# PCB_7_3D.net
KiCad netlist of a schematic drawn in EasyEDA
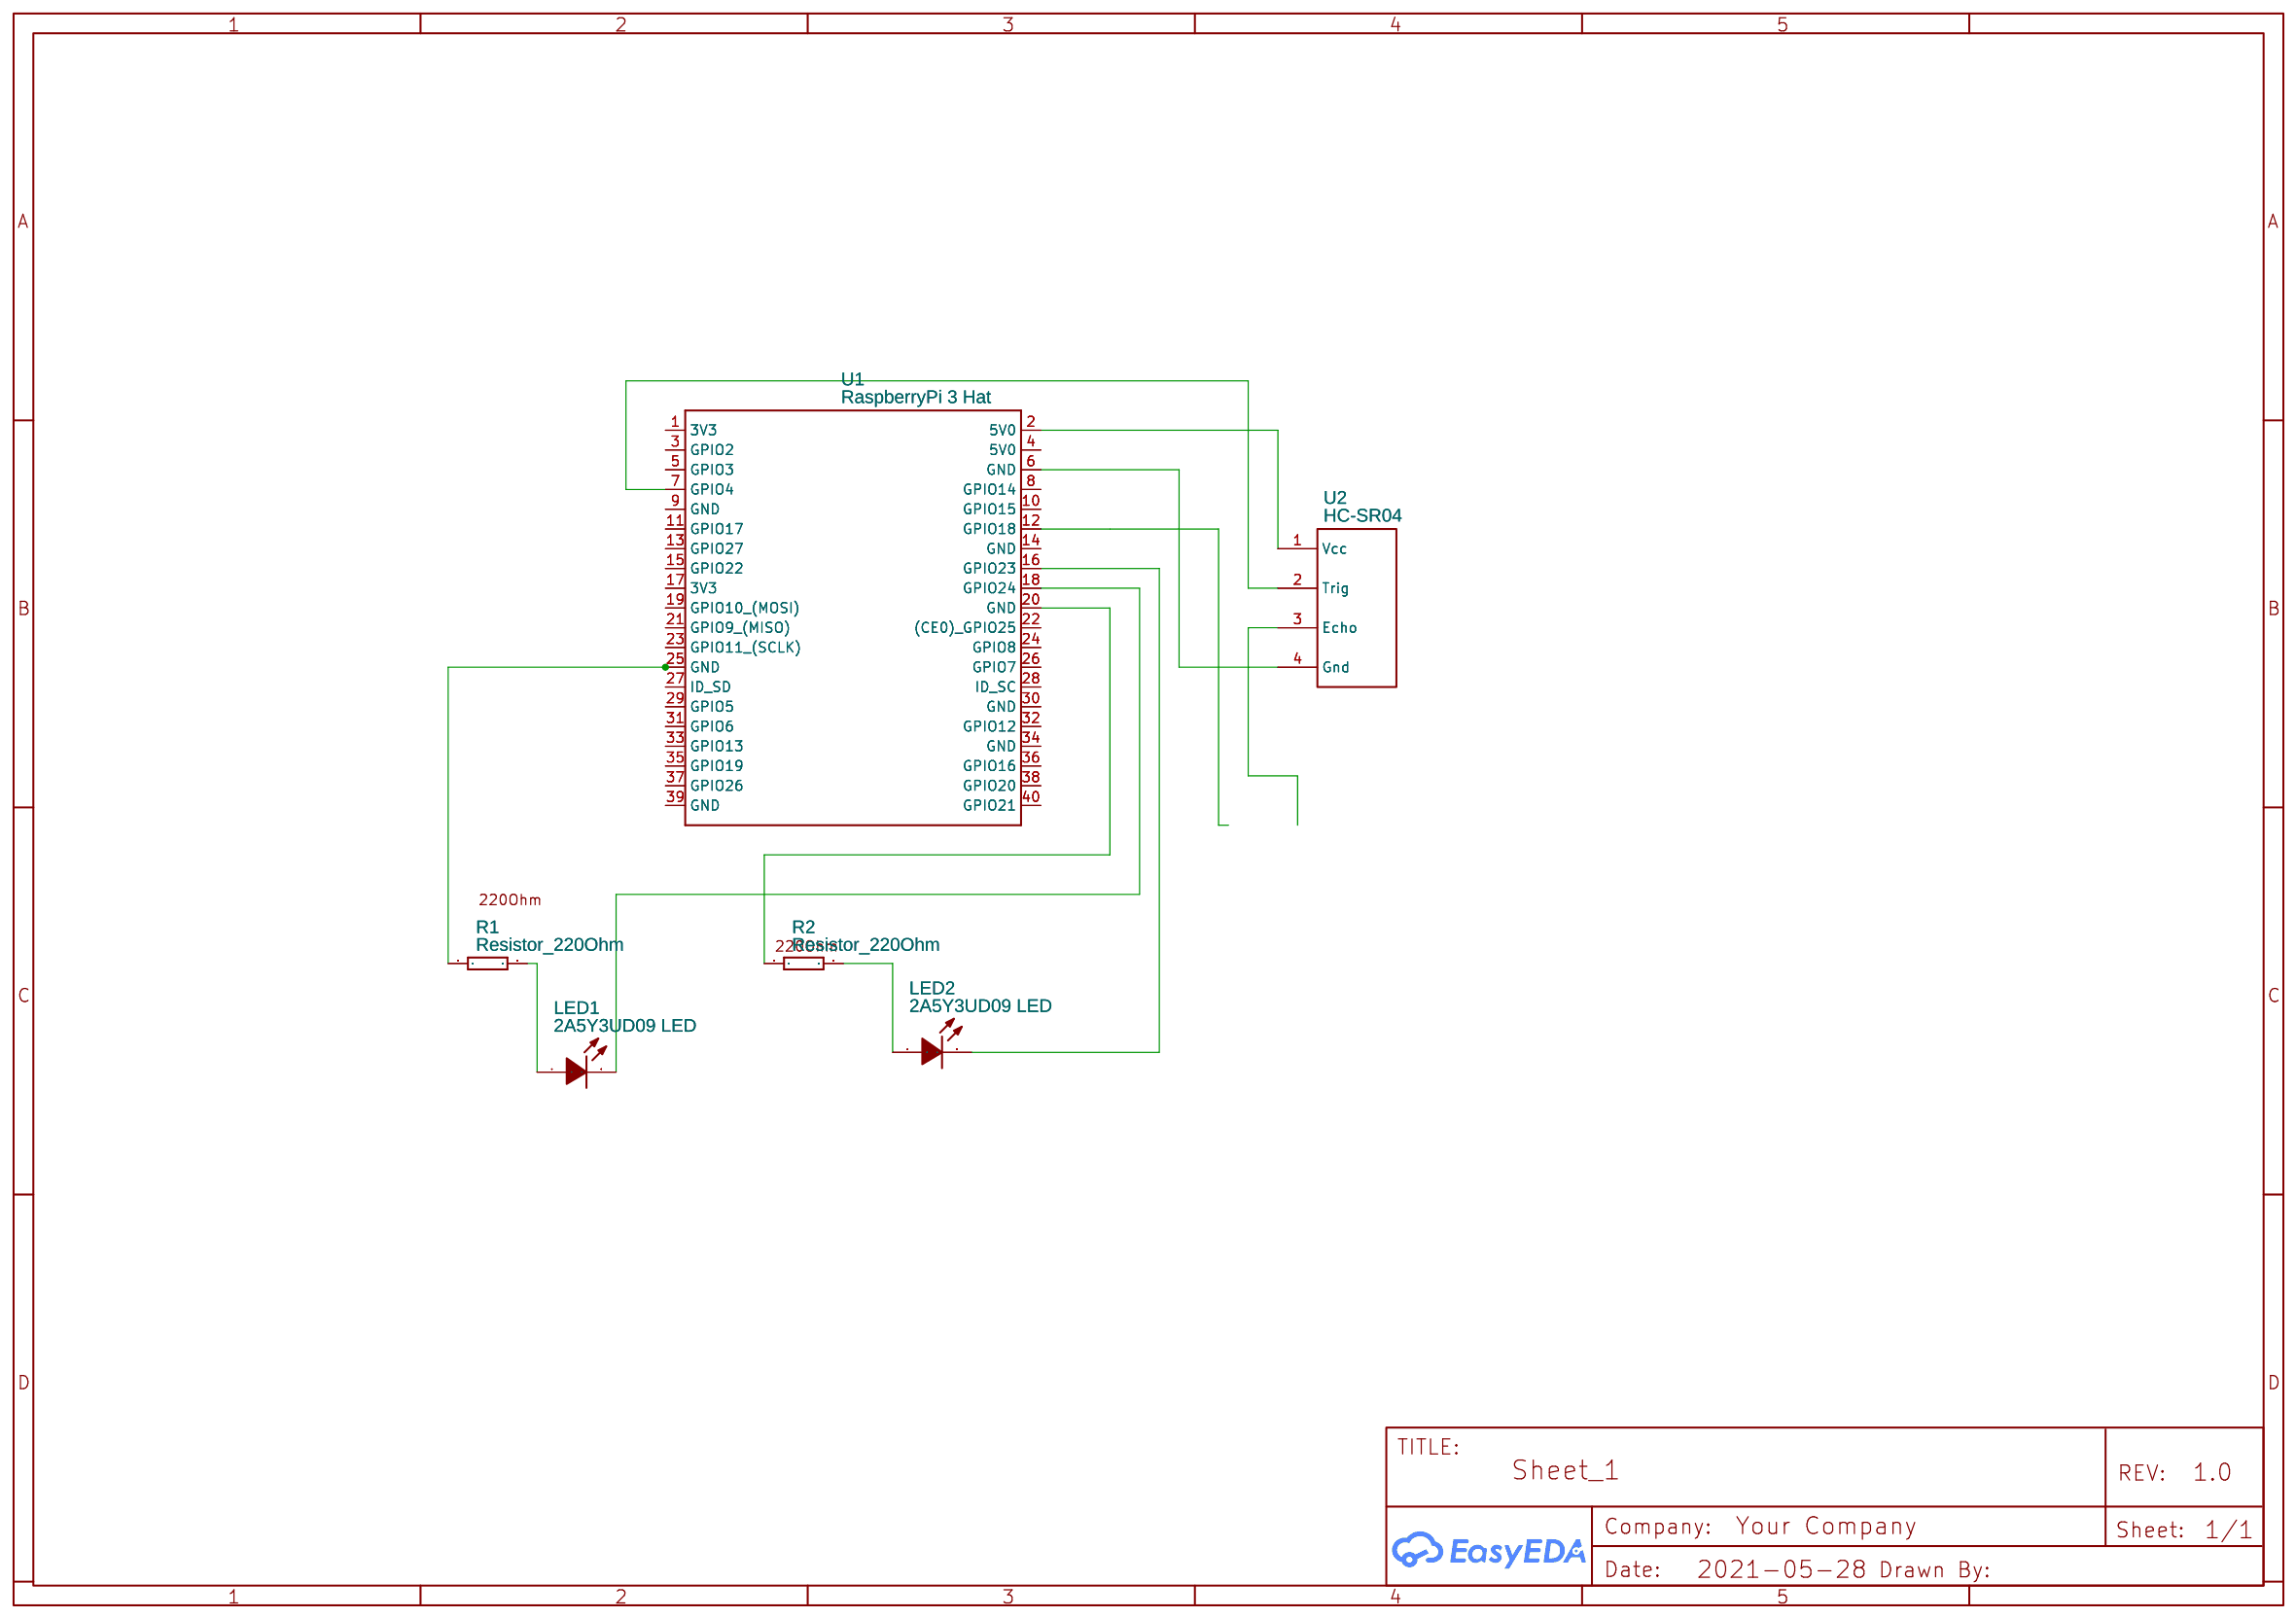
[diagram p0: schematic sheet]

(export (version "E")
  (design (tool "Eeschema 10.0.6"))
  (components
    (comp (ref "LED1")
      (value "2A5Y3UD09 LED")
      (fields (field (name "BOM_Supplier Part") "C3651"))
      (libsource (lib "") (part "2A5Y3UD09 LED"))
    )
    (comp (ref "LED2")
      (value "2A5Y3UD09 LED")
      (fields (field (name "BOM_Supplier Part") "C3651"))
      (libsource (lib "") (part "2A5Y3UD09 LED"))
    )
    (comp (ref "R1") (value "Resistor_220Ohm") (libsource (lib "") (part "Resistor_220Ohm_1")))
    (comp (ref "R2") (value "Resistor_220Ohm") (libsource (lib "") (part "Resistor_220Ohm")))
    (comp (ref "U1")
      (value "RaspberryPi 3 Hat")
      (fields (field (name "BOM_Manufacturer Part") "RaspberryPi 3"))
      (libsource (lib "") (part "RaspberryPi 3 Hat"))
    )
    (comp (ref "U2") (value "HC-SR04") (libsource (lib "") (part "HC-SR04")))
  )
  (nets
    (net (code "1") (name "Net-(LED1-+)") (class "Default")
      (node (ref "LED1") (pin "1") (pinfunction "+_1") (pintype "unspecified"))
      (node (ref "R1") (pin "2") (pinfunction "2_2") (pintype "unspecified"))
    )
    (net (code "2") (name "Net-(LED1--)") (class "Default")
      (node (ref "LED1") (pin "2") (pinfunction "-_2") (pintype "unspecified"))
      (node (ref "U1") (pin "18") (pinfunction "GPIO24_18") (pintype "unspecified"))
    )
    (net (code "3") (name "Net-(LED2-+)") (class "Default")
      (node (ref "LED2") (pin "1") (pinfunction "+_1") (pintype "unspecified"))
      (node (ref "R2") (pin "2") (pinfunction "2_2") (pintype "unspecified"))
    )
    (net (code "4") (name "Net-(LED2--)") (class "Default")
      (node (ref "LED2") (pin "2") (pinfunction "-_2") (pintype "unspecified"))
      (node (ref "U1") (pin "16") (pinfunction "GPIO23_16") (pintype "unspecified"))
    )
    (net (code "5") (name "Net-(R1-Pad1)") (class "Default")
      (node (ref "R1") (pin "1") (pinfunction "1_1") (pintype "unspecified"))
      (node (ref "U1") (pin "25") (pinfunction "GND_25") (pintype "unspecified"))
    )
    (net (code "6") (name "Net-(R2-Pad1)") (class "Default")
      (node (ref "R2") (pin "1") (pinfunction "1_1") (pintype "unspecified"))
      (node (ref "U1") (pin "20") (pinfunction "GND_20") (pintype "unspecified"))
    )
    (net (code "7") (name "Net-(U1-GPIO4)") (class "Default")
      (node (ref "U1") (pin "7") (pinfunction "GPIO4_7") (pintype "unspecified"))
      (node (ref "U2") (pin "2") (pinfunction "Trig_2") (pintype "unspecified"))
    )
    (net (code "8") (name "Net-(U2-Gnd)") (class "Default")
      (node (ref "U1") (pin "6") (pinfunction "GND_6") (pintype "unspecified"))
      (node (ref "U2") (pin "4") (pinfunction "Gnd_4") (pintype "unspecified"))
    )
    (net (code "9") (name "Net-(U2-Vcc)") (class "Default")
      (node (ref "U1") (pin "2") (pinfunction "5V0_2") (pintype "unspecified"))
      (node (ref "U2") (pin "1") (pinfunction "Vcc_1") (pintype "unspecified"))
    )
    (net (code "10") (name "unconnected-(U1-(CE0)_GPIO25-Pad22)") (class "Default")
      (node (ref "U1") (pin "22") (pinfunction "(CE0)_GPIO25_22") (pintype "unspecified"))
    )
    (net (code "11") (name "unconnected-(U1-3V3-Pad1)") (class "Default")
      (node (ref "U1") (pin "1") (pinfunction "3V3_1") (pintype "unspecified"))
    )
    (net (code "12") (name "unconnected-(U1-3V3-Pad17)") (class "Default")
      (node (ref "U1") (pin "17") (pinfunction "3V3_17") (pintype "unspecified"))
    )
    (net (code "13") (name "unconnected-(U1-5V0-Pad4)") (class "Default")
      (node (ref "U1") (pin "4") (pinfunction "5V0_4") (pintype "unspecified"))
    )
    (net (code "14") (name "unconnected-(U1-GND-Pad9)") (class "Default")
      (node (ref "U1") (pin "9") (pinfunction "GND_9") (pintype "unspecified"))
    )
    (net (code "15") (name "unconnected-(U1-GND-Pad14)") (class "Default")
      (node (ref "U1") (pin "14") (pinfunction "GND_14") (pintype "unspecified"))
    )
    (net (code "16") (name "unconnected-(U1-GND-Pad30)") (class "Default")
      (node (ref "U1") (pin "30") (pinfunction "GND_30") (pintype "unspecified"))
    )
    (net (code "17") (name "unconnected-(U1-GND-Pad34)") (class "Default")
      (node (ref "U1") (pin "34") (pinfunction "GND_34") (pintype "unspecified"))
    )
    (net (code "18") (name "unconnected-(U1-GND-Pad39)") (class "Default")
      (node (ref "U1") (pin "39") (pinfunction "GND_39") (pintype "unspecified"))
    )
    (net (code "19") (name "unconnected-(U1-GPIO2-Pad3)") (class "Default")
      (node (ref "U1") (pin "3") (pinfunction "GPIO2_3") (pintype "unspecified"))
    )
    (net (code "20") (name "unconnected-(U1-GPIO3-Pad5)") (class "Default")
      (node (ref "U1") (pin "5") (pinfunction "GPIO3_5") (pintype "unspecified"))
    )
    (net (code "21") (name "unconnected-(U1-GPIO5-Pad29)") (class "Default")
      (node (ref "U1") (pin "29") (pinfunction "GPIO5_29") (pintype "unspecified"))
    )
    (net (code "22") (name "unconnected-(U1-GPIO6-Pad31)") (class "Default")
      (node (ref "U1") (pin "31") (pinfunction "GPIO6_31") (pintype "unspecified"))
    )
    (net (code "23") (name "unconnected-(U1-GPIO7-Pad26)") (class "Default")
      (node (ref "U1") (pin "26") (pinfunction "GPIO7_26") (pintype "unspecified"))
    )
    (net (code "24") (name "unconnected-(U1-GPIO8-Pad24)") (class "Default")
      (node (ref "U1") (pin "24") (pinfunction "GPIO8_24") (pintype "unspecified"))
    )
    (net (code "25") (name "unconnected-(U1-GPIO9_(MISO)-Pad21)") (class "Default")
      (node (ref "U1") (pin "21") (pinfunction "GPIO9_(MISO)_21") (pintype "unspecified"))
    )
    (net (code "26") (name "unconnected-(U1-GPIO10_(MOSI)-Pad19)") (class "Default")
      (node (ref "U1") (pin "19") (pinfunction "GPIO10_(MOSI)_19") (pintype "unspecified"))
    )
    (net (code "27") (name "unconnected-(U1-GPIO11_(SCLK)-Pad23)") (class "Default")
      (node (ref "U1") (pin "23") (pinfunction "GPIO11_(SCLK)_23") (pintype "unspecified"))
    )
    (net (code "28") (name "unconnected-(U1-GPIO12-Pad32)") (class "Default")
      (node (ref "U1") (pin "32") (pinfunction "GPIO12_32") (pintype "unspecified"))
    )
    (net (code "29") (name "unconnected-(U1-GPIO13-Pad33)") (class "Default")
      (node (ref "U1") (pin "33") (pinfunction "GPIO13_33") (pintype "unspecified"))
    )
    (net (code "30") (name "unconnected-(U1-GPIO14-Pad8)") (class "Default")
      (node (ref "U1") (pin "8") (pinfunction "GPIO14_8") (pintype "unspecified"))
    )
    (net (code "31") (name "unconnected-(U1-GPIO15-Pad10)") (class "Default")
      (node (ref "U1") (pin "10") (pinfunction "GPIO15_10") (pintype "unspecified"))
    )
    (net (code "32") (name "unconnected-(U1-GPIO16-Pad36)") (class "Default")
      (node (ref "U1") (pin "36") (pinfunction "GPIO16_36") (pintype "unspecified"))
    )
    (net (code "33") (name "unconnected-(U1-GPIO17-Pad11)") (class "Default")
      (node (ref "U1") (pin "11") (pinfunction "GPIO17_11") (pintype "unspecified"))
    )
    (net (code "34") (name "unconnected-(U1-GPIO18-Pad12)") (class "Default")
      (node (ref "U1") (pin "12") (pinfunction "GPIO18_12") (pintype "unspecified"))
    )
    (net (code "35") (name "unconnected-(U1-GPIO19-Pad35)") (class "Default")
      (node (ref "U1") (pin "35") (pinfunction "GPIO19_35") (pintype "unspecified"))
    )
    (net (code "36") (name "unconnected-(U1-GPIO20-Pad38)") (class "Default")
      (node (ref "U1") (pin "38") (pinfunction "GPIO20_38") (pintype "unspecified"))
    )
    (net (code "37") (name "unconnected-(U1-GPIO21-Pad40)") (class "Default")
      (node (ref "U1") (pin "40") (pinfunction "GPIO21_40") (pintype "unspecified"))
    )
    (net (code "38") (name "unconnected-(U1-GPIO22-Pad15)") (class "Default")
      (node (ref "U1") (pin "15") (pinfunction "GPIO22_15") (pintype "unspecified"))
    )
    (net (code "39") (name "unconnected-(U1-GPIO26-Pad37)") (class "Default")
      (node (ref "U1") (pin "37") (pinfunction "GPIO26_37") (pintype "unspecified"))
    )
    (net (code "40") (name "unconnected-(U1-GPIO27-Pad13)") (class "Default")
      (node (ref "U1") (pin "13") (pinfunction "GPIO27_13") (pintype "unspecified"))
    )
    (net (code "41") (name "unconnected-(U1-ID_SC-Pad28)") (class "Default")
      (node (ref "U1") (pin "28") (pinfunction "ID_SC_28") (pintype "unspecified"))
    )
    (net (code "42") (name "unconnected-(U1-ID_SD-Pad27)") (class "Default")
      (node (ref "U1") (pin "27") (pinfunction "ID_SD_27") (pintype "unspecified"))
    )
    (net (code "43") (name "unconnected-(U2-Echo-Pad3)") (class "Default")
      (node (ref "U2") (pin "3") (pinfunction "Echo_3") (pintype "unspecified"))
    )
  )
)
